# optoreflector.net
KiCad netlist of a schematic drawn in EAGLE
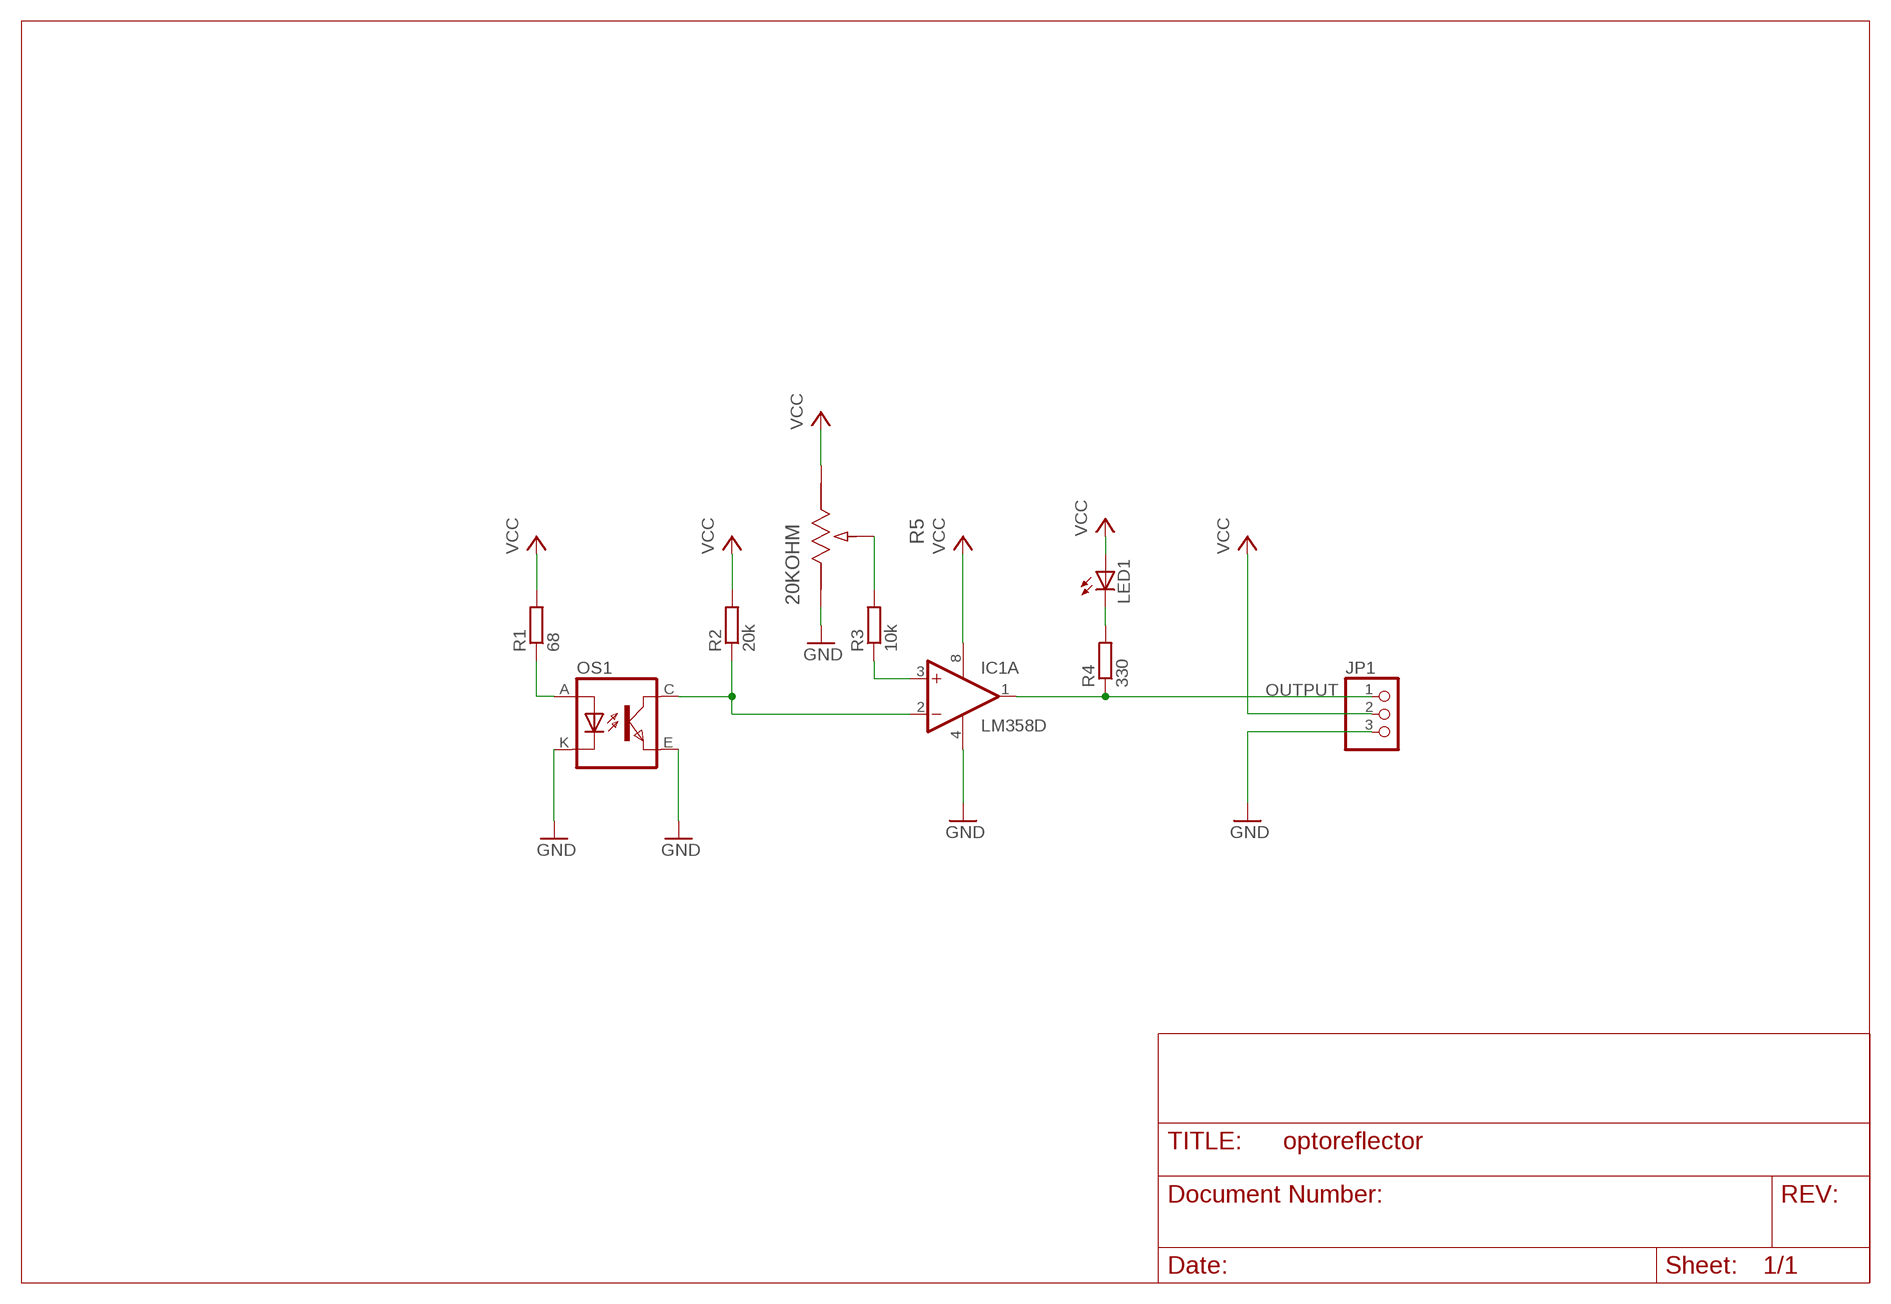
[diagram p0: schematic, sheet 1]

(export (version "E")
  (design (tool "Eeschema 10.0.6"))
  (components
    (comp (ref "IC1")
      (value "LM358D")
      (footprint "eagle-import:SO08")
      (libsource (lib "eagle-import") (part "LM358D"))
    )
    (comp (ref "JP1")
      (value "PINHD-1X3")
      (footprint "eagle-import:1X03")
      (libsource (lib "eagle-import") (part "PINHD-1X3"))
    )
    (comp (ref "LED1")
      (value "LEDCHIP-LED0805")
      (footprint "eagle-import:CHIP-LED0805")
      (libsource (lib "eagle-import") (part "LEDCHIP-LED0805"))
    )
    (comp (ref "OS1")
      (value "TCRT5000")
      (footprint "eagle-import:TCRT5000")
      (libsource (lib "eagle-import") (part "TCRT5000"))
    )
    (comp (ref "R1")
      (value "68")
      (footprint "eagle-import:R0805")
      (libsource (lib "eagle-import") (part "R-EU_R0805"))
    )
    (comp (ref "R2")
      (value "20k")
      (footprint "eagle-import:R0805")
      (libsource (lib "eagle-import") (part "R-EU_R0805"))
    )
    (comp (ref "R3")
      (value "10k")
      (footprint "eagle-import:R0805")
      (libsource (lib "eagle-import") (part "R-EU_R0805"))
    )
    (comp (ref "R4")
      (value "330")
      (footprint "eagle-import:R0805")
      (libsource (lib "eagle-import") (part "R-EU_R0805"))
    )
    (comp (ref "R5")
      (value "20KOHM")
      (footprint "eagle-import:POT_EVM2W")
      (fields (field (name "MPN") "EVM2WSX80B24") (field (name "TOLERANCE") "±25 %"))
      (libsource (lib "eagle-import") (part "EVM-2W2WSX80B24"))
    )
  )
  (nets
    (net (code "1") (name "/OUTPUT") (class "Default")
      (node (ref "IC1") (pin "1") (pinfunction "OUT_1") (pintype "output"))
      (node (ref "JP1") (pin "1") (pinfunction "1_1") (pintype "passive"))
      (node (ref "R4") (pin "1") (pinfunction "1_1") (pintype "passive"))
    )
    (net (code "2") (name "GND") (class "Default")
      (node (ref "IC1") (pin "4") (pinfunction "V-_4") (pintype "power_in"))
      (node (ref "JP1") (pin "3") (pinfunction "3_3") (pintype "passive"))
      (node (ref "OS1") (pin "E") (pinfunction "EMITTER_E") (pintype "passive"))
      (node (ref "OS1") (pin "K") (pinfunction "CATHODE_K") (pintype "passive"))
      (node (ref "R5") (pin "3") (pinfunction "3_3") (pintype "passive"))
    )
    (net (code "3") (name "Net-(IC1A-+IN)") (class "Default")
      (node (ref "IC1") (pin "3") (pinfunction "+IN_3") (pintype "input"))
      (node (ref "R3") (pin "1") (pinfunction "1_1") (pintype "passive"))
    )
    (net (code "4") (name "Net-(IC1A--IN)") (class "Default")
      (node (ref "IC1") (pin "2") (pinfunction "-IN_2") (pintype "input"))
      (node (ref "OS1") (pin "C") (pinfunction "COLLECTOR_C") (pintype "passive"))
      (node (ref "R2") (pin "1") (pinfunction "1_1") (pintype "passive"))
    )
    (net (code "5") (name "Net-(LED1-PadC)") (class "Default")
      (node (ref "LED1") (pin "C") (pinfunction "C_C") (pintype "passive"))
      (node (ref "R4") (pin "2") (pinfunction "2_2") (pintype "passive"))
    )
    (net (code "6") (name "Net-(OS1-ANODE)") (class "Default")
      (node (ref "OS1") (pin "A") (pinfunction "ANODE_A") (pintype "passive"))
      (node (ref "R1") (pin "1") (pinfunction "1_1") (pintype "passive"))
    )
    (net (code "7") (name "Net-(R3-Pad2)") (class "Default")
      (node (ref "R3") (pin "2") (pinfunction "2_2") (pintype "passive"))
      (node (ref "R5") (pin "2") (pinfunction "2_2") (pintype "passive"))
    )
    (net (code "8") (name "VCC") (class "Default")
      (node (ref "IC1") (pin "8") (pinfunction "V+_8") (pintype "power_in"))
      (node (ref "JP1") (pin "2") (pinfunction "2_2") (pintype "passive"))
      (node (ref "LED1") (pin "A") (pinfunction "A_A") (pintype "passive"))
      (node (ref "R1") (pin "2") (pinfunction "2_2") (pintype "passive"))
      (node (ref "R2") (pin "2") (pinfunction "2_2") (pintype "passive"))
      (node (ref "R5") (pin "1") (pinfunction "1_1") (pintype "passive"))
    )
  )
)
